# -20210715.net
KiCad netlist of a schematic drawn in Altium Designer
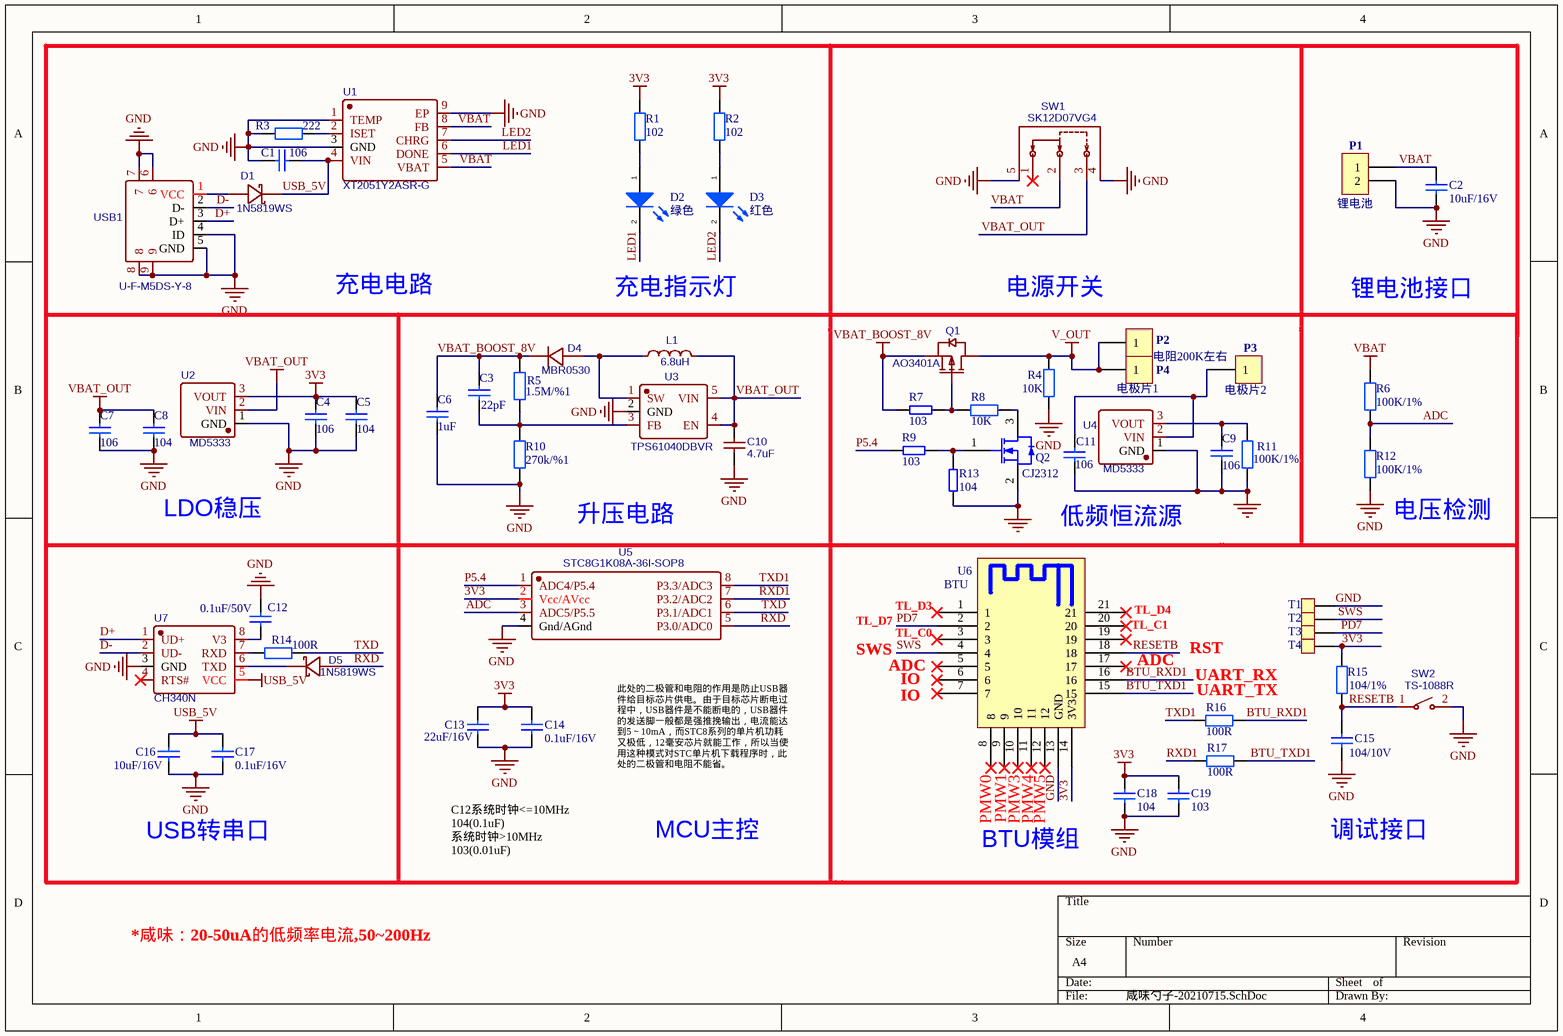
[diagram p0: 咸味勺子-20210715.SchDoc]

(export (version "E")
  (design (tool "Eeschema 10.0.6"))
  (components
    (comp (ref "C1")
      (value "106")
      (footprint "C0603")
      (description "无极性电容")
      (fields (field (name "PART NUMBER") "1.02.03.00181") (field (name "修改人") "system"))
      (libsource (lib "Database_Libs") (part "Capacitor - non polarized"))
    )
    (comp (ref "C2")
      (value "10uF/16V")
      (footprint "C0603")
      (description "无极性电容")
      (fields (field (name "PART NUMBER") "1.02.05.00869"))
      (libsource (lib "Database_Libs4") (part "Capacitor - non polarized"))
    )
    (comp (ref "C3")
      (value "22pF")
      (footprint "C0402_GRM15")
      (description "无极性电容")
      (fields (field (name "PART NUMBER") "1.02.05.00869"))
      (libsource (lib "Database_Libs4") (part "Capacitor - non polarized"))
    )
    (comp (ref "C4")
      (value "106")
      (footprint "C0603")
      (description "无极性电容")
      (fields (field (name "PART NUMBER") "1.02.05.00869"))
      (libsource (lib "Database_Libs4") (part "Capacitor - non polarized"))
    )
    (comp (ref "C5")
      (value "104")
      (footprint "C0402_GRM15")
      (description "无极性电容")
      (fields (field (name "PART NUMBER") "1.02.05.00869"))
      (libsource (lib "Database_Libs4") (part "Capacitor - non polarized"))
    )
    (comp (ref "C6")
      (value "1uF")
      (footprint "C0603")
      (description "无极性电容")
      (fields (field (name "PART NUMBER") "1.02.05.00869"))
      (libsource (lib "Database_Libs4") (part "Capacitor - non polarized"))
    )
    (comp (ref "C7")
      (value "106")
      (footprint "C0603")
      (description "无极性电容")
      (fields (field (name "PART NUMBER") "1.02.05.00869"))
      (libsource (lib "Database_Libs4") (part "Capacitor - non polarized"))
    )
    (comp (ref "C8")
      (value "104")
      (footprint "C0402_GRM15")
      (description "无极性电容")
      (fields (field (name "PART NUMBER") "1.02.05.00869"))
      (libsource (lib "Database_Libs4") (part "Capacitor - non polarized"))
    )
    (comp (ref "C9")
      (value "106")
      (footprint "C0603")
      (description "无极性电容")
      (fields (field (name "PART NUMBER") "1.02.05.00869"))
      (libsource (lib "Database_Libs4") (part "Capacitor - non polarized"))
    )
    (comp (ref "C10")
      (value "4.7uF")
      (footprint "JMK212BJ475KG-T")
      (fields
        (field (name "BOM_MANUFACTURER PART") "JMK212BJ475KG-T")
        (field (name "BOM_SUPPLIER PART") "C92788")
      )
      (libsource (lib "altium-import") (part "root_1_4.7uF_"))
    )
    (comp (ref "C11")
      (value "106")
      (footprint "C0603")
      (description "无极性电容")
      (fields (field (name "PART NUMBER") "1.02.05.00869"))
      (libsource (lib "Database_Libs4") (part "Capacitor - non polarized"))
    )
    (comp (ref "C12")
      (value "0.1uF/50V")
      (footprint "C0402_GRM15")
      (description "无极性电容")
      (fields (field (name "PART NUMBER") "1.02.05.00834") (field (name "修改人") "system"))
      (libsource (lib "Database_Libs") (part "Capacitor - non polarized"))
    )
    (comp (ref "C13")
      (value "22uF/16V")
      (footprint "C0603")
      (description "无极性电容")
      (fields (field (name "PART NUMBER") "1.02.03.00181") (field (name "修改人") "system"))
      (libsource (lib "Database_Libs") (part "Capacitor - non polarized"))
    )
    (comp (ref "C14")
      (value "0.1uF/16V")
      (footprint "C0402_GRM15")
      (description "无极性电容")
      (fields (field (name "PART NUMBER") "1.02.05.00834") (field (name "修改人") "system"))
      (libsource (lib "Database_Libs") (part "Capacitor - non polarized"))
    )
    (comp (ref "C15")
      (value "104/10V")
      (footprint "C0402_GRM15")
      (description "无极性电容")
      (fields (field (name "PART NUMBER") "1.02.05.00869"))
      (libsource (lib "Database_Libs4") (part "Capacitor - non polarized"))
    )
    (comp (ref "C16")
      (value "10uF/16V")
      (footprint "C0603")
      (description "无极性电容")
      (fields (field (name "PART NUMBER") "1.02.03.00181") (field (name "修改人") "system"))
      (libsource (lib "Database_Libs") (part "Capacitor - non polarized"))
    )
    (comp (ref "C17")
      (value "0.1uF/16V")
      (footprint "C0402_GRM15")
      (description "无极性电容")
      (fields (field (name "PART NUMBER") "1.02.05.00834") (field (name "修改人") "system"))
      (libsource (lib "Database_Libs") (part "Capacitor - non polarized"))
    )
    (comp (ref "C18")
      (value "104")
      (footprint "C0402_GRM15")
      (description "无极性电容")
      (fields (field (name "PART NUMBER") "1.02.05.00869"))
      (libsource (lib "Database_Libs4") (part "Capacitor - non polarized"))
    )
    (comp (ref "C19")
      (value "103")
      (footprint "C0402_GRM15")
      (description "无极性电容")
      (fields (field (name "PART NUMBER") "1.02.05.00869"))
      (libsource (lib "Database_Libs4") (part "Capacitor - non polarized"))
    )
    (comp (ref "D1")
      (value "1N5819WS")
      (footprint "1N5819WS")
      (fields (field (name "BOM_SUPPLIER PART") "C1884554") (field (name "CONTRIBUTOR") "LCSC"))
      (libsource (lib "altium-import") (part "root_2_1N5819WS_C1884554_"))
    )
    (comp (ref "D2")
      (value "绿色")
      (footprint "OSR50603C1E")
      (description "LED")
      (fields (field (name "PART NUMBER") "1.06.02.00452"))
      (libsource (lib "Database_Libs4") (part "LED"))
    )
    (comp (ref "D3")
      (value "红色")
      (footprint "OSR50603C1E")
      (description "LED")
      (fields (field (name "PART NUMBER") "1.06.02.00452"))
      (libsource (lib "Database_Libs4") (part "LED"))
    )
    (comp (ref "D4")
      (value "MBR0530")
      (footprint "MBR0530")
      (fields (field (name "BOM_SUPPLIER PART") "C475718") (field (name "CONTRIBUTOR") "LCSC"))
      (libsource (lib "altium-import") (part "root_0_MBR0530_C475718_"))
    )
    (comp (ref "D5")
      (value "1N5819WS")
      (footprint "1N5819WS")
      (fields (field (name "BOM_SUPPLIER PART") "C1884554") (field (name "CONTRIBUTOR") "LCSC"))
      (libsource (lib "altium-import") (part "root_0_1N5819WS_C1884554_"))
    )
    (comp (ref "L1")
      (value "6.8uH")
      (footprint "CDRH3D23NP-6R8PC")
      (fields
        (field (name "BOM_SUPPLIER PART") "C323532")
        (field (name "BOM_MANUFACTURER PART") "CDRH3D23NP-6R8PC")
        (field (name "CONTRIBUTOR") "LCSC")
      )
      (libsource (lib "altium-import") (part "root_0_6.8uH_"))
    )
    (comp (ref "P1")
      (value "锂电池")
      (footprint "1.5mm 2p接插件")
      (description "Connector")
      (libsource (lib "*") (part "CON2"))
    )
    (comp (ref "P2") (value "CON1") (footprint "焊点1") (libsource (lib "智能烧水壶 -电源板") (part "CON1")))
    (comp (ref "P3") (value "CON1") (footprint "焊点1") (libsource (lib "智能烧水壶 -电源板") (part "CON1")))
    (comp (ref "P4") (value "CON1") (footprint "焊点1") (libsource (lib "智能烧水壶 -电源板") (part "CON1")))
    (comp (ref "Q1")
      (value "AO3401A")
      (footprint "AO3401A")
      (fields (field (name "BOM_SUPPLIER PART") "C700954") (field (name "CONTRIBUTOR") "LCSC"))
      (libsource (lib "altium-import") (part "root_1_mirrored_AO3401A_C700954_"))
    )
    (comp (ref "Q2")
      (value "CJ2312")
      (footprint "CJ2312")
      (description "N-Channel MOSFET")
      (fields
        (field (name "PART NUMBER") "1.06.11.00008")
        (field (name "ORCAD LIBRARY PATH") "‪Z:\\tuya_lib\\sch-lib\\DISCRETE.OLB")
        (field (name "修改人") "system")
      )
      (libsource (lib "Database_Libs") (part "MOSFET-N"))
    )
    (comp (ref "R1")
      (value "102")
      (footprint "R0402")
      (description "电阻")
      (fields (field (name "PART NUMBER") "1.01.01.00808"))
      (libsource (lib "Database_Libs4") (part "Resistor"))
    )
    (comp (ref "R2")
      (value "102")
      (footprint "R0402")
      (description "电阻")
      (fields (field (name "PART NUMBER") "1.01.01.00808"))
      (libsource (lib "Database_Libs4") (part "Resistor"))
    )
    (comp (ref "R3")
      (value "222")
      (footprint "R0402")
      (description "电阻")
      (fields (field (name "PART NUMBER") "1.01.01.00808"))
      (libsource (lib "") (part "Resistor_1"))
    )
    (comp (ref "R4")
      (value "10K")
      (footprint "R0402")
      (description "电阻")
      (libsource (lib "") (part "Resistor_2"))
    )
    (comp (ref "R5")
      (value "1.5M/%1")
      (footprint "R0402")
      (description "电阻")
      (libsource (lib "Database_Libs") (part "Resistor"))
    )
    (comp (ref "R6")
      (value "100K/1%")
      (footprint "R0402")
      (description "电阻")
      (libsource (lib "Database_Libs") (part "Resistor"))
    )
    (comp (ref "R7")
      (value "103")
      (footprint "R0402")
      (description "RES")
      (libsource (lib "先锋器件封装库") (part "RES-1"))
    )
    (comp (ref "R8")
      (value "10K")
      (footprint "R0402")
      (description "电阻")
      (libsource (lib "") (part "Resistor_1"))
    )
    (comp (ref "R9")
      (value "103")
      (footprint "R0402")
      (description "RES")
      (libsource (lib "先锋器件封装库") (part "RES-1"))
    )
    (comp (ref "R10")
      (value "270k/%1")
      (footprint "R0402")
      (description "电阻")
      (libsource (lib "Database_Libs") (part "Resistor"))
    )
    (comp (ref "R11")
      (value "100K/1%")
      (footprint "R0402")
      (description "电阻")
      (libsource (lib "Database_Libs") (part "Resistor"))
    )
    (comp (ref "R12")
      (value "100K/1%")
      (footprint "R0402")
      (description "电阻")
      (libsource (lib "Database_Libs") (part "Resistor"))
    )
    (comp (ref "R13")
      (value "104")
      (footprint "R0402")
      (description "RES")
      (libsource (lib "先锋器件封装库") (part "RES-1"))
    )
    (comp (ref "R14")
      (value "100R")
      (footprint "R0402")
      (description "电阻")
      (fields (field (name "PART NUMBER") "1.01.01.00808") (field (name "修改人") "system"))
      (libsource (lib "") (part "Resistor_1"))
    )
    (comp (ref "R15")
      (value "104/1%")
      (footprint "R0402")
      (description "电阻")
      (fields (field (name "PART NUMBER") "1.01.01.00808"))
      (libsource (lib "Database_Libs4") (part "Resistor"))
    )
    (comp (ref "R16")
      (value "100R")
      (footprint "R0402")
      (description "电阻")
      (fields (field (name "PART NUMBER") "1.01.01.00808"))
      (libsource (lib "") (part "Resistor_1"))
    )
    (comp (ref "R17")
      (value "100R")
      (footprint "R0402")
      (description "电阻")
      (fields (field (name "PART NUMBER") "1.01.01.00808"))
      (libsource (lib "") (part "Resistor_1"))
    )
    (comp (ref "SW1")
      (value "SK12D07VG4")
      (footprint "SK12D07VG4")
      (fields (field (name "BOM_SUPPLIER PART") "C393937") (field (name "CONTRIBUTOR") "LCSC"))
      (libsource (lib "altium-import") (part "root_0_SK12D07VG4_"))
    )
    (comp (ref "SW2")
      (value "TS-1088R")
      (footprint "TS-1088R-02026")
      (fields
        (field (name "BOM_SUPPLIER PART") "C455280")
        (field (name "BOM_MANUFACTURER PART") "TS-1088R-02026")
        (field (name "CONTRIBUTOR") "LCSC")
      )
      (libsource (lib "altium-import") (part "root_0_TS-1088R-02026_"))
    )
    (comp (ref "T1") (value "TP") (footprint "TP1") (libsource (lib "MIAXIS-SCH") (part "TP")))
    (comp (ref "T2") (value "TP") (footprint "TP1") (libsource (lib "MIAXIS-SCH") (part "TP")))
    (comp (ref "T3") (value "TP") (footprint "TP1") (libsource (lib "MIAXIS-SCH") (part "TP")))
    (comp (ref "T4") (value "TP") (footprint "TP1") (libsource (lib "MIAXIS-SCH") (part "TP")))
    (comp (ref "U1")
      (value "XT2051Y2ASR-G")
      (footprint "XT2051Y2ASR-G")
      (fields (field (name "BOM_SUPPLIER PART") "C236398") (field (name "CONTRIBUTOR") "LCSC"))
      (libsource (lib "altium-import") (part "root_0_XT2051Y2ASR-G_"))
    )
    (comp (ref "U2")
      (value "MD5333")
      (footprint "MD5333")
      (fields (field (name "BOM_SUPPLIER PART") "C2827936") (field (name "CONTRIBUTOR") "LCSC"))
      (libsource (lib "altium-import") (part "root_2_MD5333_"))
    )
    (comp (ref "U3")
      (value "TPS61040DBVR")
      (footprint "TPS61040DBVR")
      (fields (field (name "BOM_SUPPLIER PART") "C7722"))
      (libsource (lib "altium-import") (part "root_0_TPS61040DBVR_"))
    )
    (comp (ref "U4")
      (value "MD5333")
      (footprint "MD5333")
      (fields (field (name "BOM_SUPPLIER PART") "C2827936") (field (name "CONTRIBUTOR") "LCSC"))
      (libsource (lib "altium-import") (part "root_2_MD5333_"))
    )
    (comp (ref "U5")
      (value "STC8G1K08A-36I-SOP8")
      (footprint "STC8G1K08A-36I-SOP8")
      (fields (field (name "BOM_SUPPLIER PART") "C915663") (field (name "CONTRIBUTOR") "LCSC"))
      (libsource (lib "altium-import") (part "root_0_STC8G1K08A-36I-SOP8_"))
    )
    (comp (ref "U6")
      (value "BTU")
      (footprint "CBU1")
      (fields (field (name "PART NUMBER") "0110"))
      (libsource (lib "BTU_V100") (part "CBU"))
    )
    (comp (ref "U7")
      (value "CH340N")
      (footprint "CH340N")
      (fields (field (name "BOM_SUPPLIER PART") "C506813") (field (name "CONTRIBUTOR") "LCSC"))
      (libsource (lib "TY") (part "CH340N"))
    )
    (comp (ref "USB1")
      (value "U-F-M5DS-Y-8")
      (footprint "U-F-M5DS-Y-8")
      (fields (field (name "BOM_SUPPLIER PART") "C961761") (field (name "CONTRIBUTOR") "LCSC"))
      (libsource (lib "altium-import") (part "root_0_U-F-M5DS-Y-8_"))
    )
  )
  (nets
    (net (code "1") (name "/ADC") (class "Default")
      (node (ref "R12") (pin "2") (pinfunction "2_2") (pintype "passive"))
      (node (ref "R6") (pin "1") (pinfunction "1_1") (pintype "passive"))
      (node (ref "U5") (pin "3") (pinfunction "ADC5/P5.5_3") (pintype "passive"))
    )
    (net (code "2") (name "/BTU_RXD1") (class "Default")
      (node (ref "R16") (pin "1") (pinfunction "1_1") (pintype "passive"))
      (node (ref "U6") (pin "16") (pinfunction "16_16") (pintype "passive"))
    )
    (net (code "3") (name "/BTU_TXD1") (class "Default")
      (node (ref "R17") (pin "1") (pinfunction "1_1") (pintype "passive"))
      (node (ref "U6") (pin "15") (pinfunction "15_15") (pintype "passive"))
    )
    (net (code "4") (name "/D+") (class "Default")
      (node (ref "U7") (pin "1") (pinfunction "UD+_1") (pintype "passive"))
      (node (ref "USB1") (pin "3") (pinfunction "D+_3") (pintype "passive"))
    )
    (net (code "5") (name "/D-") (class "Default")
      (node (ref "U7") (pin "2") (pinfunction "UD-_2") (pintype "passive"))
      (node (ref "USB1") (pin "2") (pinfunction "D-_2") (pintype "passive"))
    )
    (net (code "6") (name "/LED1") (class "Default")
      (node (ref "D2") (pin "2") (pinfunction "2_2") (pintype "passive"))
      (node (ref "U1") (pin "6") (pinfunction "DONE_6") (pintype "passive"))
    )
    (net (code "7") (name "/LED2") (class "Default")
      (node (ref "D3") (pin "2") (pinfunction "2_2") (pintype "passive"))
      (node (ref "U1") (pin "7") (pinfunction "CHRG_7") (pintype "passive"))
    )
    (net (code "8") (name "/P5.4") (class "Default")
      (node (ref "R9") (pin "1") (pintype "passive"))
      (node (ref "U5") (pin "1") (pinfunction "ADC4/P5.4_1") (pintype "passive"))
    )
    (net (code "9") (name "/PD7") (class "Default")
      (node (ref "T3") (pin "1") (pinfunction "1_1") (pintype "passive"))
      (node (ref "U6") (pin "2") (pinfunction "2_2") (pintype "passive"))
    )
    (net (code "10") (name "/RESETB") (class "Default")
      (node (ref "C15") (pin "1") (pinfunction "1_1") (pintype "passive"))
      (node (ref "R15") (pin "1") (pinfunction "1_1") (pintype "passive"))
      (node (ref "SW2") (pin "1") (pinfunction "1_1") (pintype "passive"))
      (node (ref "U6") (pin "18") (pinfunction "18_18") (pintype "passive"))
    )
    (net (code "11") (name "/RXD") (class "Default")
      (node (ref "D5") (pin "2") (pinfunction "A_2") (pintype "passive"))
      (node (ref "U5") (pin "5") (pinfunction "P3.0/ADC0_5") (pintype "passive"))
    )
    (net (code "12") (name "/RXD1") (class "Default")
      (node (ref "R17") (pin "2") (pinfunction "2_2") (pintype "passive"))
      (node (ref "U5") (pin "7") (pinfunction "P3.2/ADC2_7") (pintype "passive"))
    )
    (net (code "13") (name "/SWS") (class "Default")
      (node (ref "T2") (pin "1") (pinfunction "1_1") (pintype "passive"))
      (node (ref "U6") (pin "4") (pinfunction "4_4") (pintype "passive"))
    )
    (net (code "14") (name "/TXD") (class "Default")
      (node (ref "R14") (pin "2") (pinfunction "2_2") (pintype "passive"))
      (node (ref "U5") (pin "6") (pinfunction "P3.1/ADC1_6") (pintype "passive"))
    )
    (net (code "15") (name "/TXD1") (class "Default")
      (node (ref "R16") (pin "2") (pinfunction "2_2") (pintype "passive"))
      (node (ref "U5") (pin "8") (pinfunction "P3.3/ADC3_8") (pintype "passive"))
    )
    (net (code "16") (name "3V3") (class "Default")
      (node (ref "C13") (pin "2") (pinfunction "2_2") (pintype "passive"))
      (node (ref "C14") (pin "2") (pinfunction "2_2") (pintype "passive"))
      (node (ref "C18") (pin "1") (pinfunction "1_1") (pintype "passive"))
      (node (ref "C19") (pin "1") (pinfunction "1_1") (pintype "passive"))
      (node (ref "C4") (pin "1") (pinfunction "1_1") (pintype "passive"))
      (node (ref "C5") (pin "1") (pinfunction "1_1") (pintype "passive"))
      (node (ref "R1") (pin "2") (pinfunction "2_2") (pintype "passive"))
      (node (ref "R15") (pin "2") (pinfunction "2_2") (pintype "passive"))
      (node (ref "R2") (pin "2") (pinfunction "2_2") (pintype "passive"))
      (node (ref "T4") (pin "1") (pinfunction "1_1") (pintype "passive"))
      (node (ref "U2") (pin "3") (pinfunction "VOUT_3") (pintype "passive"))
      (node (ref "U5") (pin "2") (pinfunction "Vcc/AVcc_2") (pintype "passive"))
      (node (ref "U6") (pin "14") (pinfunction "3V3_14") (pintype "passive"))
    )
    (net (code "17") (name "GND") (class "Default")
      (node (ref "C1") (pin "2") (pinfunction "2_2") (pintype "passive"))
      (node (ref "C10") (pin "1") (pinfunction "1_1") (pintype "passive"))
      (node (ref "C11") (pin "2") (pinfunction "2_2") (pintype "passive"))
      (node (ref "C12") (pin "2") (pinfunction "2_2") (pintype "passive"))
      (node (ref "C13") (pin "1") (pinfunction "1_1") (pintype "passive"))
      (node (ref "C14") (pin "1") (pinfunction "1_1") (pintype "passive"))
      (node (ref "C15") (pin "2") (pinfunction "2_2") (pintype "passive"))
      (node (ref "C16") (pin "1") (pinfunction "1_1") (pintype "passive"))
      (node (ref "C17") (pin "1") (pinfunction "1_1") (pintype "passive"))
      (node (ref "C18") (pin "2") (pinfunction "2_2") (pintype "passive"))
      (node (ref "C19") (pin "2") (pinfunction "2_2") (pintype "passive"))
      (node (ref "C2") (pin "2") (pinfunction "2_2") (pintype "passive"))
      (node (ref "C4") (pin "2") (pinfunction "2_2") (pintype "passive"))
      (node (ref "C5") (pin "2") (pinfunction "2_2") (pintype "passive"))
      (node (ref "C6") (pin "2") (pinfunction "2_2") (pintype "passive"))
      (node (ref "C7") (pin "2") (pinfunction "2_2") (pintype "passive"))
      (node (ref "C8") (pin "2") (pinfunction "2_2") (pintype "passive"))
      (node (ref "C9") (pin "2") (pinfunction "2_2") (pintype "passive"))
      (node (ref "P1") (pin "2") (pinfunction "2_2") (pintype "passive"))
      (node (ref "Q2") (pin "2") (pinfunction "S_2") (pintype "passive"))
      (node (ref "R10") (pin "1") (pinfunction "1_1") (pintype "passive"))
      (node (ref "R11") (pin "1") (pinfunction "1_1") (pintype "passive"))
      (node (ref "R12") (pin "1") (pinfunction "1_1") (pintype "passive"))
      (node (ref "R13") (pin "1") (pintype "passive"))
      (node (ref "R3") (pin "2") (pinfunction "2_2") (pintype "passive"))
      (node (ref "R4") (pin "2") (pinfunction "2_2") (pintype "passive"))
      (node (ref "SW1") (pin "4") (pinfunction "4_4") (pintype "passive"))
      (node (ref "SW1") (pin "5") (pinfunction "5_5") (pintype "passive"))
      (node (ref "SW2") (pin "2") (pinfunction "2_2") (pintype "passive"))
      (node (ref "T1") (pin "1") (pinfunction "1_1") (pintype "passive"))
      (node (ref "U1") (pin "1") (pinfunction "TEMP_1") (pintype "passive"))
      (node (ref "U1") (pin "3") (pinfunction "GND_3") (pintype "passive"))
      (node (ref "U1") (pin "9") (pinfunction "EP_9") (pintype "passive"))
      (node (ref "U2") (pin "1") (pinfunction "GND_1") (pintype "passive"))
      (node (ref "U3") (pin "2") (pinfunction "GND_2") (pintype "passive"))
      (node (ref "U4") (pin "1") (pinfunction "GND_1") (pintype "passive"))
      (node (ref "U5") (pin "4") (pinfunction "Gnd/AGnd_4") (pintype "passive"))
      (node (ref "U6") (pin "13") (pinfunction "GND_13") (pintype "passive"))
      (node (ref "U7") (pin "3") (pinfunction "GND_3") (pintype "passive"))
      (node (ref "USB1") (pin "4") (pinfunction "ID_4") (pintype "passive"))
      (node (ref "USB1") (pin "5") (pinfunction "GND_5") (pintype "passive"))
      (node (ref "USB1") (pin "6") (pinfunction "6_6") (pintype "passive"))
      (node (ref "USB1") (pin "7") (pinfunction "7_7") (pintype "passive"))
      (node (ref "USB1") (pin "8") (pinfunction "8_8") (pintype "passive"))
      (node (ref "USB1") (pin "9") (pinfunction "9_9") (pintype "passive"))
    )
    (net (code "18") (name "Net-(D1-A)") (class "Default")
      (node (ref "D1") (pin "2") (pinfunction "A_2") (pintype "passive"))
      (node (ref "USB1") (pin "1") (pinfunction "VCC_1") (pintype "passive"))
    )
    (net (code "19") (name "Net-(D2-Pad1)") (class "Default")
      (node (ref "D2") (pin "1") (pinfunction "1_1") (pintype "passive"))
      (node (ref "R1") (pin "1") (pinfunction "1_1") (pintype "passive"))
    )
    (net (code "20") (name "Net-(D3-Pad1)") (class "Default")
      (node (ref "D3") (pin "1") (pinfunction "1_1") (pintype "passive"))
      (node (ref "R2") (pin "1") (pinfunction "1_1") (pintype "passive"))
    )
    (net (code "21") (name "Net-(D4-A)") (class "Default")
      (node (ref "D4") (pin "2") (pinfunction "A_2") (pintype "passive"))
      (node (ref "L1") (pin "1") (pinfunction "1_1") (pintype "passive"))
      (node (ref "U3") (pin "1") (pinfunction "SW_1") (pintype "passive"))
    )
    (net (code "22") (name "Net-(D5-C)") (class "Default")
      (node (ref "D5") (pin "1") (pinfunction "C_1") (pintype "passive"))
      (node (ref "U7") (pin "6") (pinfunction "TXD_6") (pintype "passive"))
    )
    (net (code "23") (name "Net-(Q1-G)") (class "Default")
      (node (ref "Q1") (pin "1") (pinfunction "G_1") (pintype "passive"))
      (node (ref "R7") (pin "2") (pintype "passive"))
      (node (ref "R8") (pin "1") (pinfunction "1_1") (pintype "passive"))
    )
    (net (code "24") (name "Net-(Q2-D)") (class "Default")
      (node (ref "Q2") (pin "3") (pinfunction "D_3") (pintype "passive"))
      (node (ref "R8") (pin "2") (pinfunction "2_2") (pintype "passive"))
    )
    (net (code "25") (name "Net-(Q2-G)") (class "Default")
      (node (ref "Q2") (pin "1") (pinfunction "G_1") (pintype "passive"))
      (node (ref "R13") (pin "2") (pintype "passive"))
      (node (ref "R9") (pin "2") (pintype "passive"))
    )
    (net (code "26") (name "Net-(U1-ISET)") (class "Default")
      (node (ref "R3") (pin "1") (pinfunction "1_1") (pintype "passive"))
      (node (ref "U1") (pin "2") (pinfunction "ISET_2") (pintype "passive"))
    )
    (net (code "27") (name "Net-(U3-FB)") (class "Default")
      (node (ref "C3") (pin "2") (pinfunction "2_2") (pintype "passive"))
      (node (ref "R10") (pin "2") (pinfunction "2_2") (pintype "passive"))
      (node (ref "R5") (pin "1") (pinfunction "1_1") (pintype "passive"))
      (node (ref "U3") (pin "3") (pinfunction "FB_3") (pintype "passive"))
    )
    (net (code "28") (name "Net-(U4-VIN)") (class "Default")
      (node (ref "C11") (pin "1") (pinfunction "1_1") (pintype "passive"))
      (node (ref "P3") (pin "1") (pinfunction "1_1") (pintype "passive"))
      (node (ref "U4") (pin "2") (pinfunction "VIN_2") (pintype "passive"))
    )
    (net (code "29") (name "Net-(U4-VOUT)") (class "Default")
      (node (ref "C9") (pin "1") (pinfunction "1_1") (pintype "passive"))
      (node (ref "R11") (pin "2") (pinfunction "2_2") (pintype "passive"))
      (node (ref "U4") (pin "3") (pinfunction "VOUT_3") (pintype "passive"))
    )
    (net (code "30") (name "Net-(U7-RXD)") (class "Default")
      (node (ref "R14") (pin "1") (pinfunction "1_1") (pintype "passive"))
      (node (ref "U7") (pin "7") (pinfunction "RXD_7") (pintype "passive"))
    )
    (net (code "31") (name "Net-(U7-V3)") (class "Default")
      (node (ref "C12") (pin "1") (pinfunction "1_1") (pintype "passive"))
      (node (ref "U7") (pin "8") (pinfunction "V3_8") (pintype "passive"))
    )
    (net (code "32") (name "USB_5V") (class "Default")
      (node (ref "C1") (pin "1") (pinfunction "1_1") (pintype "passive"))
      (node (ref "C16") (pin "2") (pinfunction "2_2") (pintype "passive"))
      (node (ref "C17") (pin "2") (pinfunction "2_2") (pintype "passive"))
      (node (ref "D1") (pin "1") (pinfunction "C_1") (pintype "passive"))
      (node (ref "U1") (pin "4") (pinfunction "VIN_4") (pintype "passive"))
      (node (ref "U7") (pin "5") (pinfunction "VCC_5") (pintype "passive"))
    )
    (net (code "33") (name "VBAT") (class "Default")
      (node (ref "C2") (pin "1") (pinfunction "1_1") (pintype "passive"))
      (node (ref "P1") (pin "1") (pinfunction "1_1") (pintype "passive"))
      (node (ref "R6") (pin "2") (pinfunction "2_2") (pintype "passive"))
      (node (ref "SW1") (pin "2") (pinfunction "2_2") (pintype "passive"))
      (node (ref "U1") (pin "5") (pinfunction "VBAT_5") (pintype "passive"))
      (node (ref "U1") (pin "8") (pinfunction "FB_8") (pintype "passive"))
    )
    (net (code "34") (name "VBAT_BOOST_8V") (class "Default")
      (node (ref "C3") (pin "1") (pinfunction "1_1") (pintype "passive"))
      (node (ref "C6") (pin "1") (pinfunction "1_1") (pintype "passive"))
      (node (ref "D4") (pin "1") (pinfunction "K_1") (pintype "passive"))
      (node (ref "Q1") (pin "2") (pinfunction "S_2") (pintype "passive"))
      (node (ref "R5") (pin "2") (pinfunction "2_2") (pintype "passive"))
      (node (ref "R7") (pin "1") (pintype "passive"))
    )
    (net (code "35") (name "VBAT_OUT") (class "Default")
      (node (ref "C10") (pin "2") (pinfunction "2_2") (pintype "passive"))
      (node (ref "C7") (pin "1") (pinfunction "1_1") (pintype "passive"))
      (node (ref "C8") (pin "1") (pinfunction "1_1") (pintype "passive"))
      (node (ref "L1") (pin "2") (pinfunction "2_2") (pintype "passive"))
      (node (ref "SW1") (pin "3") (pinfunction "3_3") (pintype "passive"))
      (node (ref "U2") (pin "2") (pinfunction "VIN_2") (pintype "passive"))
      (node (ref "U3") (pin "4") (pinfunction "EN_4") (pintype "passive"))
      (node (ref "U3") (pin "5") (pinfunction "VIN_5") (pintype "passive"))
    )
    (net (code "36") (name "V_OUT") (class "Default")
      (node (ref "P2") (pin "1") (pinfunction "1_1") (pintype "passive"))
      (node (ref "P4") (pin "1") (pinfunction "1_1") (pintype "passive"))
      (node (ref "Q1") (pin "3") (pinfunction "D_3") (pintype "passive"))
      (node (ref "R4") (pin "1") (pinfunction "1_1") (pintype "passive"))
    )
    (net (code "37") (name "unconnected-(SW1-Pad1)") (class "Default")
      (node (ref "SW1") (pin "1") (pinfunction "1_1") (pintype "passive+no_connect"))
    )
    (net (code "38") (name "unconnected-(U6-Pad1)") (class "Default")
      (node (ref "U6") (pin "1") (pinfunction "1_1") (pintype "passive+no_connect"))
    )
    (net (code "39") (name "unconnected-(U6-Pad3)") (class "Default")
      (node (ref "U6") (pin "3") (pinfunction "3_3") (pintype "passive+no_connect"))
    )
    (net (code "40") (name "unconnected-(U6-Pad5)") (class "Default")
      (node (ref "U6") (pin "5") (pinfunction "5_5") (pintype "passive+no_connect"))
    )
    (net (code "41") (name "unconnected-(U6-Pad6)") (class "Default")
      (node (ref "U6") (pin "6") (pinfunction "6_6") (pintype "passive+no_connect"))
    )
    (net (code "42") (name "unconnected-(U6-Pad7)") (class "Default")
      (node (ref "U6") (pin "7") (pinfunction "7_7") (pintype "passive+no_connect"))
    )
    (net (code "43") (name "unconnected-(U6-Pad8)") (class "Default")
      (node (ref "U6") (pin "8") (pinfunction "8_8") (pintype "passive+no_connect"))
    )
    (net (code "44") (name "unconnected-(U6-Pad9)") (class "Default")
      (node (ref "U6") (pin "9") (pinfunction "9_9") (pintype "passive+no_connect"))
    )
    (net (code "45") (name "unconnected-(U6-Pad10)") (class "Default")
      (node (ref "U6") (pin "10") (pinfunction "10_10") (pintype "passive+no_connect"))
    )
    (net (code "46") (name "unconnected-(U6-Pad11)") (class "Default")
      (node (ref "U6") (pin "11") (pinfunction "11_11") (pintype "passive+no_connect"))
    )
    (net (code "47") (name "unconnected-(U6-Pad12)") (class "Default")
      (node (ref "U6") (pin "12") (pinfunction "12_12") (pintype "passive+no_connect"))
    )
    (net (code "48") (name "unconnected-(U6-Pad17)") (class "Default")
      (node (ref "U6") (pin "17") (pinfunction "17_17") (pintype "passive+no_connect"))
    )
    (net (code "49") (name "unconnected-(U6-Pad19)") (class "Default")
      (node (ref "U6") (pin "19") (pinfunction "19_19") (pintype "passive+no_connect"))
    )
    (net (code "50") (name "unconnected-(U6-Pad20)") (class "Default")
      (node (ref "U6") (pin "20") (pinfunction "20_20") (pintype "passive+no_connect"))
    )
    (net (code "51") (name "unconnected-(U6-Pad21)") (class "Default")
      (node (ref "U6") (pin "21") (pinfunction "21_21") (pintype "passive+no_connect"))
    )
    (net (code "52") (name "unconnected-(U7-RTS#-Pad4)") (class "Default")
      (node (ref "U7") (pin "4") (pinfunction "RTS#_4") (pintype "passive+no_connect"))
    )
  )
)
